# microcontroller-esp32.net
KiCad netlist of a schematic drawn in EAGLE
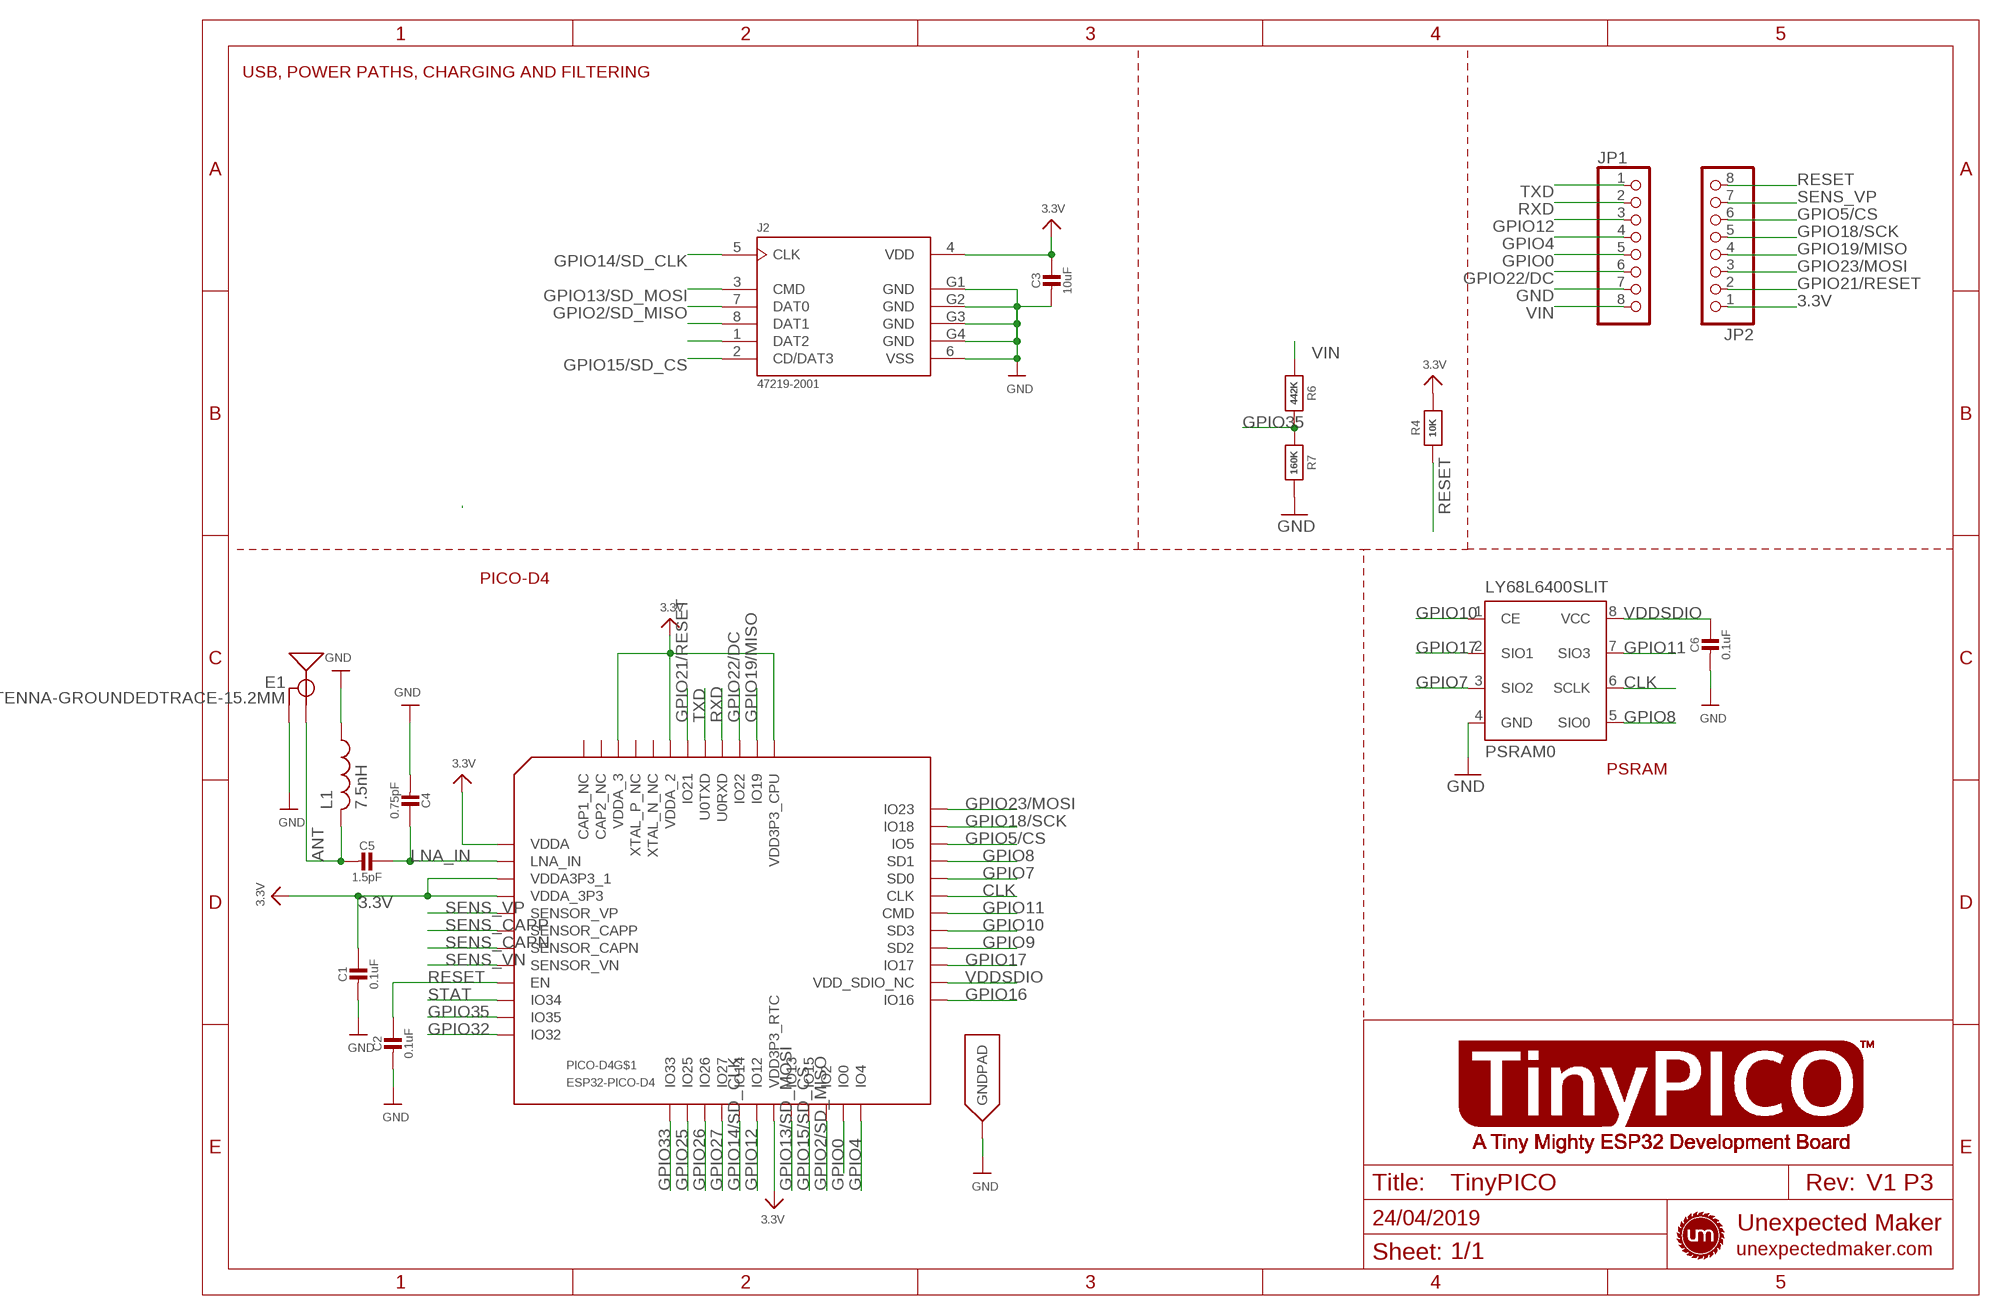
[diagram p0: schematic, sheet 1]

(export (version "E")
  (design (tool "Eeschema 10.0.6"))
  (components
    (comp (ref "C1")
      (value "0.1uF")
      (footprint "eagle-import:_0402MP")
      (libsource (lib "eagle-import") (part "CAP_CERAMIC_0402MP"))
    )
    (comp (ref "C2")
      (value "0.1uF")
      (footprint "eagle-import:_0402MP")
      (libsource (lib "eagle-import") (part "CAP_CERAMIC_0402MP"))
    )
    (comp (ref "C3")
      (value "10uF")
      (footprint "eagle-import:_0402MP")
      (libsource (lib "eagle-import") (part "CAP_CERAMIC_0402MP"))
    )
    (comp (ref "C4")
      (value "0.75pF")
      (footprint "eagle-import:_0402MP")
      (libsource (lib "eagle-import") (part "CAP_CERAMIC_0402MP"))
    )
    (comp (ref "C5")
      (value "1.5pF")
      (footprint "eagle-import:_0402MP")
      (libsource (lib "eagle-import") (part "CAP_CERAMIC_0402MP"))
    )
    (comp (ref "C6")
      (value "0.1uF")
      (footprint "eagle-import:_0402MP")
      (libsource (lib "eagle-import") (part "CAP_CERAMIC_0402MP"))
    )
    (comp (ref "E1")
      (value "ANTENNA-GROUNDEDTRACE-15.2MM")
      (footprint "eagle-import:TRACE_ANTENNA_2.4GHZ_15.2MM")
      (libsource (lib "eagle-import") (part "ANTENNA-GROUNDEDTRACE-15.2MM"))
    )
    (comp (ref "J2")
      (value "47219-2001")
      (footprint "eagle-import:MOLEX_47219-2001")
      (fields (field (name "MF") "Molex"))
      (libsource (lib "eagle-import") (part "47219-2001"))
    )
    (comp (ref "JP1")
      (value "PINHD-1X8CLEANBIG")
      (footprint "eagle-import:1X08-CLEANBIG")
      (fields (field (name "MPN") "83-15410"))
      (libsource (lib "eagle-import") (part "PINHD-1X8CLEANBIG"))
    )
    (comp (ref "JP2")
      (value "PINHD-1X8CLEANBIG")
      (footprint "eagle-import:1X08-CLEANBIG")
      (fields (field (name "MPN") "83-15410"))
      (libsource (lib "eagle-import") (part "PINHD-1X8CLEANBIG"))
    )
    (comp (ref "L1")
      (value "7.5nH")
      (footprint "eagle-import:RESC0402_N")
      (libsource (lib "eagle-import") (part "INDUCTOR_0402_N"))
    )
    (comp (ref "LY68L6400SLIT")
      (value "PSRAM0")
      (footprint "eagle-import:SOP8")
      (fields (field (name "MPN") "BD6230F-E2"))
      (libsource (lib "eagle-import") (part "PSRAM0"))
    )
    (comp (ref "PICO-D4")
      (value "ESP32-PICO-D4")
      (footprint "eagle-import:PICO-D4-QFN48")
      (libsource (lib "eagle-import") (part "ESP32-PICO-D4"))
    )
    (comp (ref "R4")
      (value "10K")
      (footprint "eagle-import:_0402MP")
      (libsource (lib "eagle-import") (part "RESISTOR_0402MP"))
    )
    (comp (ref "R6")
      (value "442K")
      (footprint "eagle-import:_0402MP")
      (libsource (lib "eagle-import") (part "RESISTOR_0402MP"))
    )
    (comp (ref "R7")
      (value "160K")
      (footprint "eagle-import:_0402MP")
      (libsource (lib "eagle-import") (part "RESISTOR_0402MP"))
    )
  )
  (nets
    (net (code "1") (name "/ANT") (class "Default")
      (node (ref "C5") (pin "2") (pinfunction "2_2") (pintype "passive"))
      (node (ref "E1") (pin "ANT") (pinfunction "SIGNAL_ANT") (pintype "bidirectional"))
      (node (ref "L1") (pin "2") (pinfunction "2_2") (pintype "passive"))
    )
    (net (code "2") (name "/CLK") (class "Default")
      (node (ref "LY68L6400SLIT") (pin "6") (pinfunction "SCLK_6") (pintype "passive"))
      (node (ref "PICO-D4") (pin "31") (pinfunction "CLK_31") (pintype "bidirectional"))
    )
    (net (code "3") (name "/GPIO0") (class "Default")
      (node (ref "JP1") (pin "5") (pinfunction "5_5") (pintype "passive"))
      (node (ref "PICO-D4") (pin "23") (pinfunction "IO0_23") (pintype "bidirectional"))
    )
    (net (code "4") (name "/GPIO2{slash}SD_MISO") (class "Default")
      (node (ref "J2") (pin "7") (pinfunction "DAT0_7") (pintype "bidirectional"))
      (node (ref "PICO-D4") (pin "22") (pinfunction "IO2_22") (pintype "bidirectional"))
    )
    (net (code "5") (name "/GPIO4") (class "Default")
      (node (ref "JP1") (pin "4") (pinfunction "4_4") (pintype "passive"))
      (node (ref "PICO-D4") (pin "24") (pinfunction "IO4_24") (pintype "bidirectional"))
    )
    (net (code "6") (name "/GPIO5{slash}CS") (class "Default")
      (node (ref "JP2") (pin "6") (pinfunction "6_6") (pintype "passive"))
      (node (ref "PICO-D4") (pin "34") (pinfunction "IO5_34") (pintype "bidirectional"))
    )
    (net (code "7") (name "/GPIO7") (class "Default")
      (node (ref "LY68L6400SLIT") (pin "3") (pinfunction "SIO2_3") (pintype "power_in"))
      (node (ref "PICO-D4") (pin "32") (pinfunction "SD0_32") (pintype "bidirectional"))
    )
    (net (code "8") (name "/GPIO8") (class "Default")
      (node (ref "LY68L6400SLIT") (pin "5") (pinfunction "SIO0_5") (pintype "input"))
      (node (ref "PICO-D4") (pin "33") (pinfunction "SD1_33") (pintype "bidirectional"))
    )
    (net (code "9") (name "/GPIO9") (class "Default")
      (node (ref "PICO-D4") (pin "28") (pinfunction "SD2_28") (pintype "bidirectional"))
    )
    (net (code "10") (name "/GPIO10") (class "Default")
      (node (ref "LY68L6400SLIT") (pin "1") (pinfunction "CE_1") (pintype "output"))
      (node (ref "PICO-D4") (pin "29") (pinfunction "SD3_29") (pintype "bidirectional"))
    )
    (net (code "11") (name "/GPIO11") (class "Default")
      (node (ref "LY68L6400SLIT") (pin "7") (pinfunction "SIO3_7") (pintype "output"))
      (node (ref "PICO-D4") (pin "30") (pinfunction "CMD_30") (pintype "bidirectional"))
    )
    (net (code "12") (name "/GPIO12") (class "Default")
      (node (ref "JP1") (pin "3") (pinfunction "3_3") (pintype "passive"))
      (node (ref "PICO-D4") (pin "18") (pinfunction "IO12_18") (pintype "power_in"))
    )
    (net (code "13") (name "/GPIO13{slash}SD_MOSI") (class "Default")
      (node (ref "J2") (pin "3") (pinfunction "CMD_3") (pintype "bidirectional"))
      (node (ref "PICO-D4") (pin "20") (pinfunction "IO13_20") (pintype "bidirectional"))
    )
    (net (code "14") (name "/GPIO14{slash}SD_CLK") (class "Default")
      (node (ref "J2") (pin "5") (pinfunction "CLK_5") (pintype "input"))
      (node (ref "PICO-D4") (pin "17") (pinfunction "IO14_17") (pintype "bidirectional"))
    )
    (net (code "15") (name "/GPIO15{slash}SD_CS") (class "Default")
      (node (ref "J2") (pin "2") (pinfunction "CD/DAT3_2") (pintype "bidirectional"))
      (node (ref "PICO-D4") (pin "21") (pinfunction "IO15_21") (pintype "bidirectional"))
    )
    (net (code "16") (name "/GPIO16") (class "Default")
      (node (ref "PICO-D4") (pin "25") (pinfunction "IO16_25") (pintype "bidirectional"))
    )
    (net (code "17") (name "/GPIO17") (class "Default")
      (node (ref "LY68L6400SLIT") (pin "2") (pinfunction "SIO1_2") (pintype "power_in"))
      (node (ref "PICO-D4") (pin "27") (pinfunction "IO17_27") (pintype "bidirectional"))
    )
    (net (code "18") (name "/GPIO18{slash}SCK") (class "Default")
      (node (ref "JP2") (pin "5") (pinfunction "5_5") (pintype "passive"))
      (node (ref "PICO-D4") (pin "35") (pinfunction "IO18_35") (pintype "bidirectional"))
    )
    (net (code "19") (name "/GPIO19{slash}MISO") (class "Default")
      (node (ref "JP2") (pin "4") (pinfunction "4_4") (pintype "passive"))
      (node (ref "PICO-D4") (pin "38") (pinfunction "IO19_38") (pintype "bidirectional"))
    )
    (net (code "20") (name "/GPIO21{slash}RESET") (class "Default")
      (node (ref "JP2") (pin "2") (pinfunction "2_2") (pintype "passive"))
      (node (ref "PICO-D4") (pin "42") (pinfunction "IO21_42") (pintype "power_in"))
    )
    (net (code "21") (name "/GPIO22{slash}DC") (class "Default")
      (node (ref "JP1") (pin "6") (pinfunction "6_6") (pintype "passive"))
      (node (ref "PICO-D4") (pin "39") (pinfunction "IO22_39") (pintype "bidirectional"))
    )
    (net (code "22") (name "/GPIO23{slash}MOSI") (class "Default")
      (node (ref "JP2") (pin "3") (pinfunction "3_3") (pintype "passive"))
      (node (ref "PICO-D4") (pin "36") (pinfunction "IO23_36") (pintype "bidirectional"))
    )
    (net (code "23") (name "/GPIO25") (class "Default")
      (node (ref "PICO-D4") (pin "14") (pinfunction "IO25_14") (pintype "bidirectional"))
    )
    (net (code "24") (name "/GPIO26") (class "Default")
      (node (ref "PICO-D4") (pin "15") (pinfunction "IO26_15") (pintype "bidirectional"))
    )
    (net (code "25") (name "/GPIO27") (class "Default")
      (node (ref "PICO-D4") (pin "16") (pinfunction "IO27_16") (pintype "bidirectional"))
    )
    (net (code "26") (name "/GPIO32") (class "Default")
      (node (ref "PICO-D4") (pin "12") (pinfunction "IO32_12") (pintype "bidirectional"))
    )
    (net (code "27") (name "/GPIO33") (class "Default")
      (node (ref "PICO-D4") (pin "13") (pinfunction "IO33_13") (pintype "bidirectional"))
    )
    (net (code "28") (name "/GPIO35") (class "Default")
      (node (ref "PICO-D4") (pin "11") (pinfunction "IO35_11") (pintype "bidirectional"))
      (node (ref "R6") (pin "2") (pinfunction "2_2") (pintype "passive"))
      (node (ref "R7") (pin "1") (pinfunction "1_1") (pintype "passive"))
    )
    (net (code "29") (name "/LNA_IN") (class "Default")
      (node (ref "C4") (pin "1") (pinfunction "1_1") (pintype "passive"))
      (node (ref "C5") (pin "1") (pinfunction "1_1") (pintype "passive"))
      (node (ref "PICO-D4") (pin "2") (pinfunction "LNA_IN_2") (pintype "bidirectional"))
    )
    (net (code "30") (name "/RESET") (class "Default")
      (node (ref "C2") (pin "1") (pinfunction "1_1") (pintype "passive"))
      (node (ref "JP2") (pin "8") (pinfunction "8_8") (pintype "passive"))
      (node (ref "PICO-D4") (pin "9") (pinfunction "EN_9") (pintype "bidirectional"))
      (node (ref "R4") (pin "1") (pinfunction "1_1") (pintype "passive"))
    )
    (net (code "31") (name "/RXD") (class "Default")
      (node (ref "JP1") (pin "2") (pinfunction "2_2") (pintype "passive"))
      (node (ref "PICO-D4") (pin "40") (pinfunction "U0RXD_40") (pintype "bidirectional"))
    )
    (net (code "32") (name "/SENS_CAPN") (class "Default")
      (node (ref "PICO-D4") (pin "7") (pinfunction "SENSOR_CAPN_7") (pintype "power_in"))
    )
    (net (code "33") (name "/SENS_CAPP") (class "Default")
      (node (ref "PICO-D4") (pin "6") (pinfunction "SENSOR_CAPP_6") (pintype "bidirectional"))
    )
    (net (code "34") (name "/SENS_VN") (class "Default")
      (node (ref "PICO-D4") (pin "8") (pinfunction "SENSOR_VN_8") (pintype "bidirectional"))
    )
    (net (code "35") (name "/SENS_VP") (class "Default")
      (node (ref "JP2") (pin "7") (pinfunction "7_7") (pintype "passive"))
      (node (ref "PICO-D4") (pin "5") (pinfunction "SENSOR_VP_5") (pintype "bidirectional"))
    )
    (net (code "36") (name "/STAT") (class "Default")
      (node (ref "PICO-D4") (pin "10") (pinfunction "IO34_10") (pintype "bidirectional"))
    )
    (net (code "37") (name "/TXD") (class "Default")
      (node (ref "JP1") (pin "1") (pinfunction "1_1") (pintype "passive"))
      (node (ref "PICO-D4") (pin "41") (pinfunction "U0TXD_41") (pintype "bidirectional"))
    )
    (net (code "38") (name "/VDDSDIO") (class "Default")
      (node (ref "C6") (pin "1") (pinfunction "1_1") (pintype "passive"))
      (node (ref "LY68L6400SLIT") (pin "8") (pinfunction "VCC_8") (pintype "power_in"))
      (node (ref "PICO-D4") (pin "26") (pinfunction "VDD_SDIO_NC_26") (pintype "bidirectional"))
    )
    (net (code "39") (name "/VIN") (class "Default")
      (node (ref "JP1") (pin "8") (pinfunction "8_8") (pintype "passive"))
      (node (ref "R6") (pin "1") (pinfunction "1_1") (pintype "passive"))
    )
    (net (code "40") (name "3.3V") (class "Default")
      (node (ref "C1") (pin "1") (pinfunction "1_1") (pintype "passive"))
      (node (ref "C3") (pin "1") (pinfunction "1_1") (pintype "passive"))
      (node (ref "J2") (pin "4") (pinfunction "VDD_4") (pintype "power_in"))
      (node (ref "JP2") (pin "1") (pinfunction "1_1") (pintype "passive"))
      (node (ref "PICO-D4") (pin "1") (pinfunction "VDDA_1") (pintype "bidirectional"))
      (node (ref "PICO-D4") (pin "19") (pinfunction "VDD3P3_RTC_19") (pintype "bidirectional"))
      (node (ref "PICO-D4") (pin "3") (pinfunction "VDDA3P3_1_3") (pintype "bidirectional"))
      (node (ref "PICO-D4") (pin "37") (pinfunction "VDD3P3_CPU_37") (pintype "bidirectional"))
      (node (ref "PICO-D4") (pin "4") (pinfunction "VDDA_3P3_4") (pintype "bidirectional"))
      (node (ref "PICO-D4") (pin "43") (pinfunction "VDDA_2_43") (pintype "bidirectional"))
      (node (ref "PICO-D4") (pin "46") (pinfunction "VDDA_3_46") (pintype "bidirectional"))
      (node (ref "R4") (pin "2") (pinfunction "2_2") (pintype "passive"))
    )
    (net (code "41") (name "GND") (class "Default")
      (node (ref "C1") (pin "2") (pinfunction "2_2") (pintype "passive"))
      (node (ref "C2") (pin "2") (pinfunction "2_2") (pintype "passive"))
      (node (ref "C3") (pin "2") (pinfunction "2_2") (pintype "passive"))
      (node (ref "C4") (pin "2") (pinfunction "2_2") (pintype "passive"))
      (node (ref "C6") (pin "2") (pinfunction "2_2") (pintype "passive"))
      (node (ref "E1") (pin "GND") (pinfunction "GND_GND") (pintype "bidirectional"))
      (node (ref "J2") (pin "6") (pinfunction "VSS_6") (pintype "power_in"))
      (node (ref "J2") (pin "G1") (pinfunction "GND_G1") (pintype "power_in"))
      (node (ref "J2") (pin "G2") (pinfunction "GND_G2") (pintype "power_in"))
      (node (ref "J2") (pin "G3") (pinfunction "GND_G3") (pintype "power_in"))
      (node (ref "J2") (pin "G4") (pinfunction "GND_G4") (pintype "power_in"))
      (node (ref "JP1") (pin "7") (pinfunction "7_7") (pintype "passive"))
      (node (ref "L1") (pin "1") (pinfunction "1_1") (pintype "passive"))
      (node (ref "LY68L6400SLIT") (pin "4") (pinfunction "GND_4") (pintype "input"))
      (node (ref "PICO-D4") (pin "EXP") (pinfunction "GNDPAD_EXP") (pintype "power_in"))
      (node (ref "R7") (pin "2") (pinfunction "2_2") (pintype "passive"))
    )
    (net (code "42") (name "unconnected-(J2-DAT1-Pad8)") (class "Default")
      (node (ref "J2") (pin "8") (pinfunction "DAT1_8") (pintype "bidirectional"))
    )
    (net (code "43") (name "unconnected-(J2-DAT2-Pad1)") (class "Default")
      (node (ref "J2") (pin "1") (pinfunction "DAT2_1") (pintype "bidirectional"))
    )
    (net (code "44") (name "unconnected-(PICO-D4A-CAP1_NC-Pad48)") (class "Default")
      (node (ref "PICO-D4") (pin "48") (pinfunction "CAP1_NC_48") (pintype "bidirectional"))
    )
    (net (code "45") (name "unconnected-(PICO-D4A-CAP2_NC-Pad47)") (class "Default")
      (node (ref "PICO-D4") (pin "47") (pinfunction "CAP2_NC_47") (pintype "bidirectional"))
    )
    (net (code "46") (name "unconnected-(PICO-D4A-XTAL_N_NC-Pad44)") (class "Default")
      (node (ref "PICO-D4") (pin "44") (pinfunction "XTAL_N_NC_44") (pintype "bidirectional"))
    )
    (net (code "47") (name "unconnected-(PICO-D4A-XTAL_P_NC-Pad45)") (class "Default")
      (node (ref "PICO-D4") (pin "45") (pinfunction "XTAL_P_NC_45") (pintype "bidirectional"))
    )
  )
)
